# LKS_DEMO_V5_0.net
KiCad netlist of a schematic drawn in Altium Designer
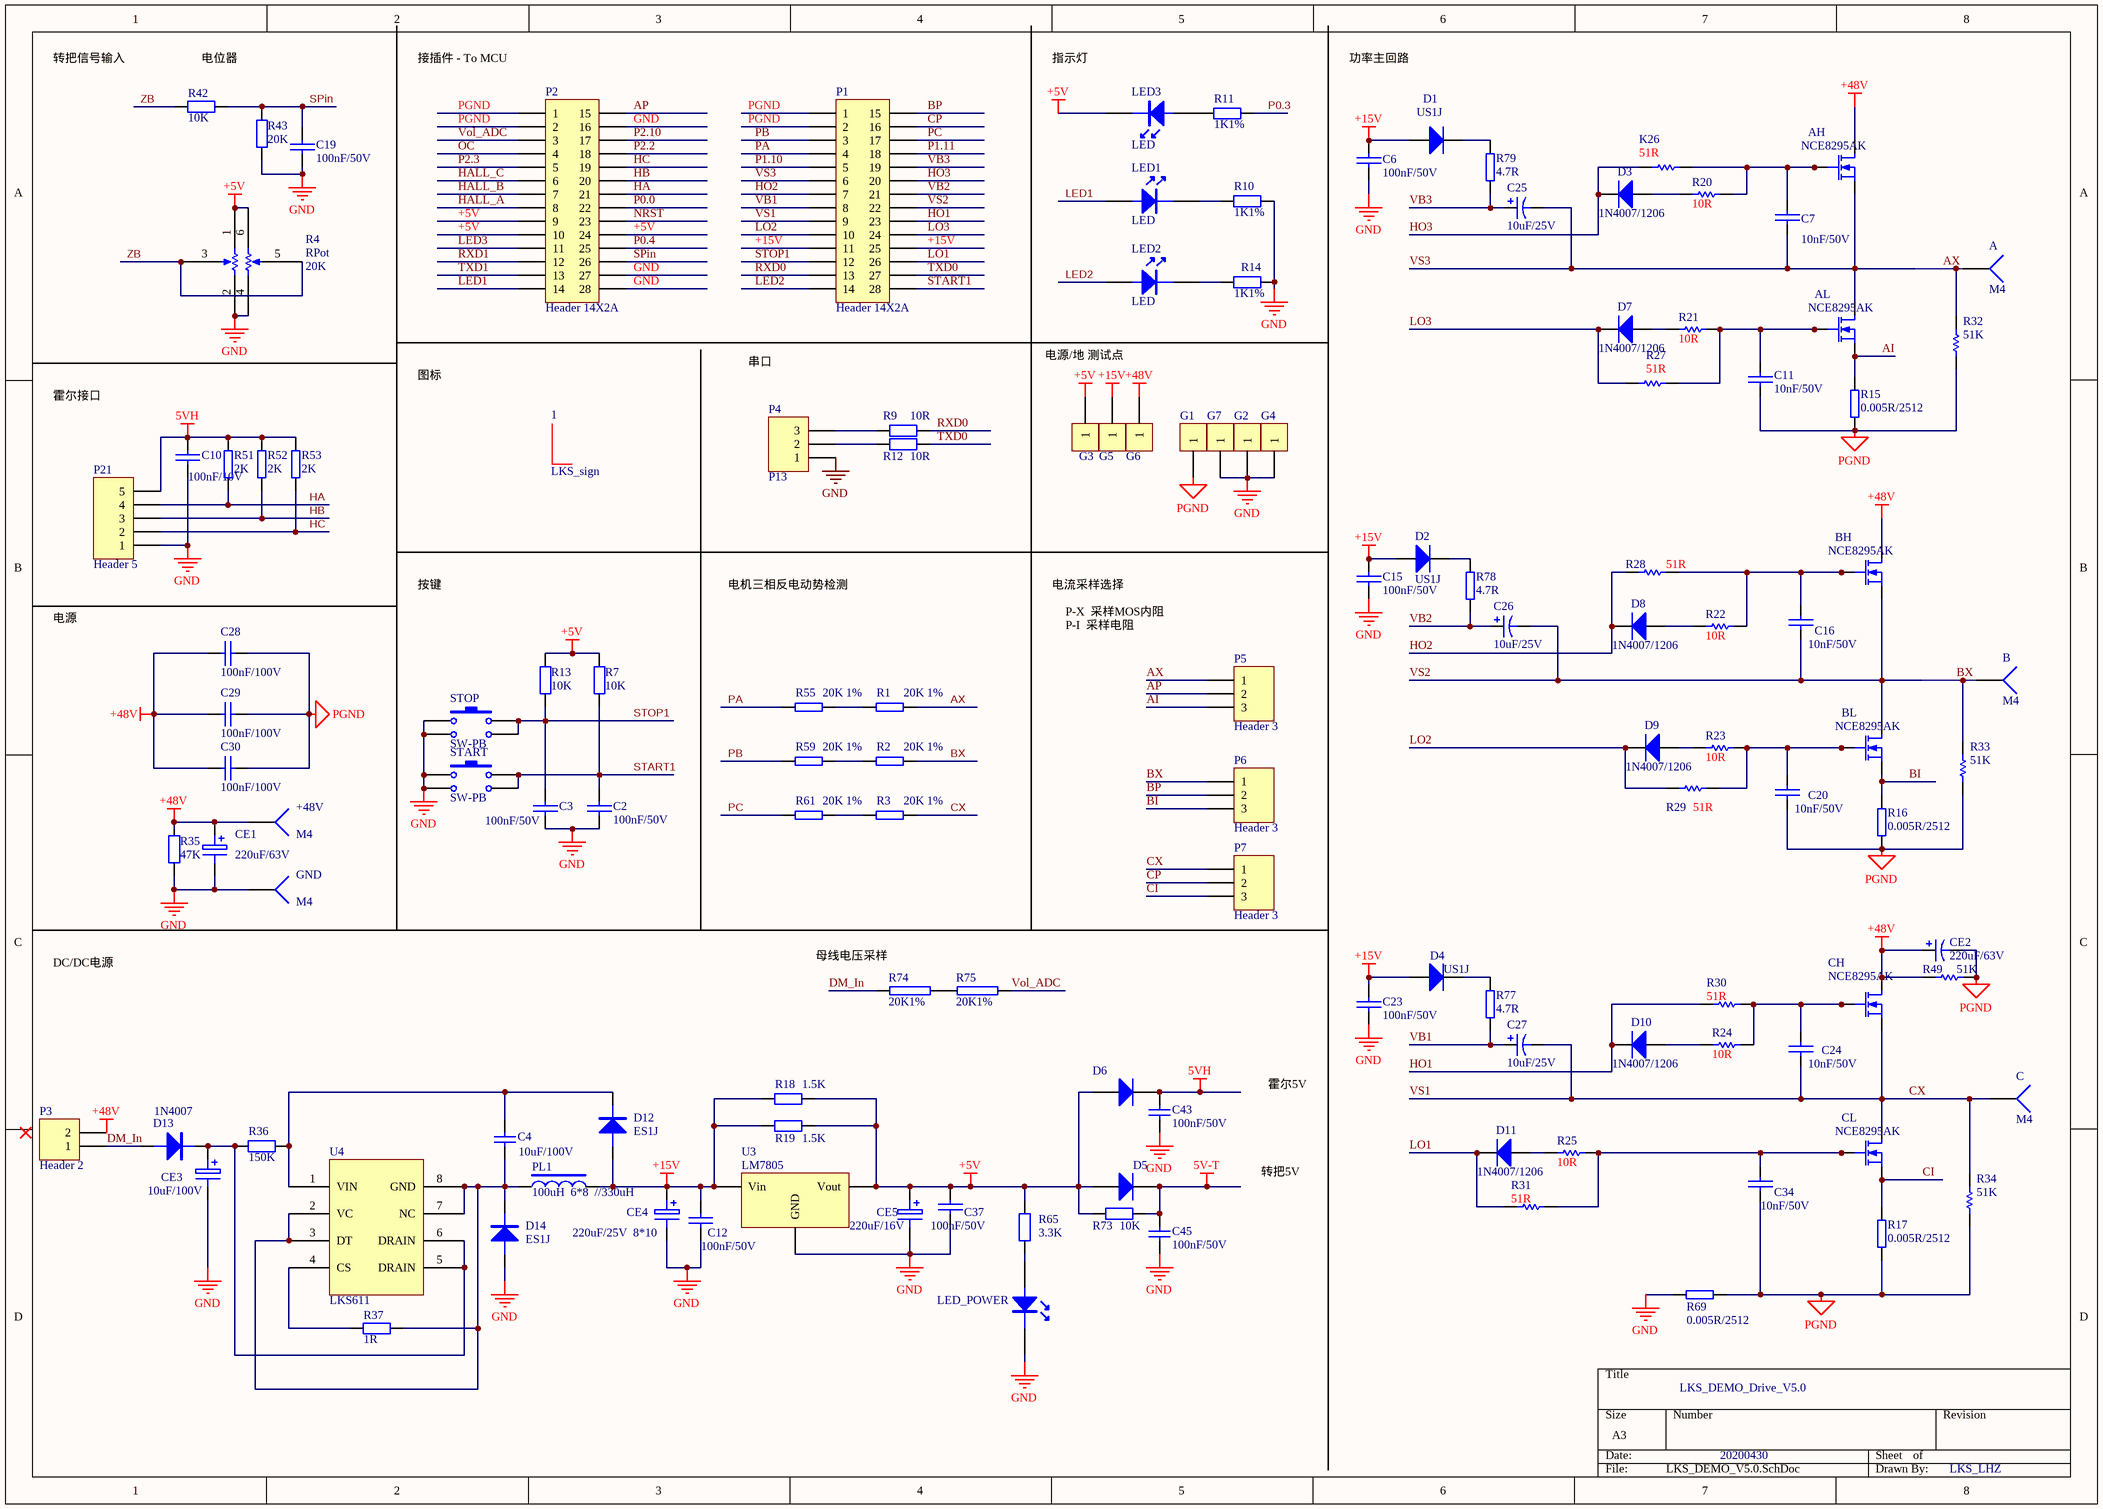
[diagram p0: LKS_DEMO_V5.0.SchDoc]

(export (version "E")
  (design (tool "Eeschema 10.0.6"))
  (components
    (comp (ref "+48V")
      (value "M4")
      (footprint "M4_Conector")
      (description "Socket")
      (fields (field (name "PUBLISHER") "Altium Limited"))
      (libsource (lib "*") (part "Socket"))
    )
    (comp (ref "1")
      (value "LKS_sign")
      (footprint "LKS_LOGO2")
      (libsource (lib "linko sch library") (part "LKS_sign"))
    )
    (comp (ref "A")
      (value "M4")
      (footprint "M4_Conector")
      (description "Socket")
      (fields (field (name "PUBLISHER") "Altium Limited"))
      (libsource (lib "*") (part "Socket"))
    )
    (comp (ref "AH")
      (value "NCE8295AK")
      (footprint "TO-252")
      (libsource (lib "POWER-conponent") (part "MOS"))
    )
    (comp (ref "AL")
      (value "NCE8295AK")
      (footprint "TO-252")
      (libsource (lib "POWER-conponent") (part "MOS"))
    )
    (comp (ref "B")
      (value "M4")
      (footprint "M4_Conector")
      (description "Socket")
      (fields (field (name "PUBLISHER") "Altium Limited"))
      (libsource (lib "*") (part "Socket"))
    )
    (comp (ref "BH")
      (value "NCE8295AK")
      (footprint "TO-252")
      (libsource (lib "POWER-conponent") (part "MOS"))
    )
    (comp (ref "BL")
      (value "NCE8295AK")
      (footprint "TO-252")
      (libsource (lib "POWER-conponent") (part "MOS"))
    )
    (comp (ref "C")
      (value "M4")
      (footprint "M4_Conector")
      (description "Socket")
      (fields (field (name "PUBLISHER") "Altium Limited"))
      (libsource (lib "*") (part "Socket"))
    )
    (comp (ref "C2")
      (value "100nF/50V")
      (footprint "0603C")
      (description "Capacitor")
      (libsource (lib "GJ-BC-IC") (part "CAP"))
    )
    (comp (ref "C3")
      (value "100nF/50V")
      (footprint "0603C")
      (description "Capacitor")
      (libsource (lib "GJ-BC-IC") (part "CAP"))
    )
    (comp (ref "C4")
      (value "10uF/100V")
      (footprint "1206")
      (description "Capacitor")
      (fields (field (name "PUBLISHER") "Altium Limited"))
      (libsource (lib "Miscellaneous Devices") (part "Cap"))
    )
    (comp (ref "C6")
      (value "100nF/50V")
      (footprint "0603C")
      (description "Capacitor")
      (libsource (lib "*") (part "C"))
    )
    (comp (ref "C7")
      (value "10nF/50V")
      (footprint "0603C")
      (description "Capacitor")
      (libsource (lib "") (part "CAP_1"))
    )
    (comp (ref "C10")
      (value "100nF/10V")
      (footprint "0603C")
      (description "Capacitor")
      (libsource (lib "GJ-BC-IC") (part "CAP"))
    )
    (comp (ref "C11")
      (value "10nF/50V")
      (footprint "0603C")
      (description "Capacitor")
      (libsource (lib "") (part "CAP_1"))
    )
    (comp (ref "C12")
      (value "100nF/50V")
      (footprint "0603C")
      (description "Capacitor")
      (libsource (lib "*") (part "CAP"))
    )
    (comp (ref "C15")
      (value "100nF/50V")
      (footprint "0603C")
      (description "Capacitor")
      (libsource (lib "*") (part "C"))
    )
    (comp (ref "C16")
      (value "10nF/50V")
      (footprint "0603C")
      (description "Capacitor")
      (libsource (lib "") (part "CAP_1"))
    )
    (comp (ref "C19")
      (value "100nF/50V")
      (footprint "0603C")
      (description "Capacitor")
      (libsource (lib "*") (part "C"))
    )
    (comp (ref "C20")
      (value "10nF/50V")
      (footprint "0603C")
      (description "Capacitor")
      (libsource (lib "") (part "CAP_1"))
    )
    (comp (ref "C23")
      (value "100nF/50V")
      (footprint "0603C")
      (description "Capacitor")
      (libsource (lib "*") (part "C"))
    )
    (comp (ref "C24")
      (value "10nF/50V")
      (footprint "0603C")
      (description "Capacitor")
      (libsource (lib "") (part "CAP_1"))
    )
    (comp (ref "C25")
      (value "10uF/25V")
      (footprint "1206")
      (description "Polarized Capacitor (Radial)")
      (fields (field (name "PUBLISHER") "Altium Limited"))
      (libsource (lib "*") (part "Cap Pol1"))
    )
    (comp (ref "C26")
      (value "10uF/25V")
      (footprint "1206")
      (description "Polarized Capacitor (Radial)")
      (fields (field (name "PUBLISHER") "Altium Limited"))
      (libsource (lib "*") (part "Cap Pol1"))
    )
    (comp (ref "C27")
      (value "10uF/25V")
      (footprint "1206")
      (description "Polarized Capacitor (Radial)")
      (fields (field (name "PUBLISHER") "Altium Limited"))
      (libsource (lib "*") (part "Cap Pol1"))
    )
    (comp (ref "C28")
      (value "100nF/100V")
      (footprint "0805C")
      (description "Capacitor")
      (libsource (lib "*") (part "CAP"))
    )
    (comp (ref "C29")
      (value "100nF/100V")
      (footprint "0805C")
      (description "Capacitor")
      (libsource (lib "*") (part "CAP"))
    )
    (comp (ref "C30")
      (value "100nF/100V")
      (footprint "0805C")
      (description "Capacitor")
      (libsource (lib "*") (part "CAP"))
    )
    (comp (ref "C34")
      (value "10nF/50V")
      (footprint "0603C")
      (description "Capacitor")
      (libsource (lib "") (part "CAP_1"))
    )
    (comp (ref "C37")
      (value "100nF/50V")
      (footprint "0603C")
      (description "Capacitor")
      (libsource (lib "*") (part "C"))
    )
    (comp (ref "C43")
      (value "100nF/50V")
      (footprint "0603C")
      (description "Capacitor")
      (fields (field (name "PUBLISHER") "Altium Limited"))
      (libsource (lib "Miscellaneous Devices") (part "Cap"))
    )
    (comp (ref "C45")
      (value "100nF/50V")
      (footprint "0603C")
      (description "Capacitor")
      (fields (field (name "PUBLISHER") "Altium Limited"))
      (libsource (lib "Miscellaneous Devices") (part "Cap"))
    )
    (comp (ref "CE1")
      (value "220uF/63V")
      (footprint "220uF/25V 12.5*12.5")
      (description "Electrolytic Capacitor")
      (libsource (lib "*") (part "CD"))
    )
    (comp (ref "CE2")
      (value "220uF/63V")
      (footprint "220uF/25V 12.5*12.5")
      (description "Polarized Capacitor (Radial)")
      (fields (field (name "PUBLISHER") "Altium Limited"))
      (libsource (lib "Miscellaneous Devices") (part "Cap Pol1"))
    )
    (comp (ref "CE3")
      (value "10uF/100V")
      (footprint "220UF/25V paster8*10")
      (description "Electrolytic Capacitor")
      (libsource (lib "*") (part "CD"))
    )
    (comp (ref "CE4")
      (value "220uF/25V  8*10")
      (footprint "220UF/25V paster8*10")
      (description "Electrolytic Capacitor")
      (libsource (lib "*") (part "CD"))
    )
    (comp (ref "CE5")
      (value "220uF/16V")
      (footprint "220UF/16V paster6.3*7.7 - duplicate")
      (description "Electrolytic Capacitor")
      (libsource (lib "*") (part "CD"))
    )
    (comp (ref "CH")
      (value "NCE8295AK")
      (footprint "TO-252")
      (libsource (lib "POWER-conponent") (part "MOS"))
    )
    (comp (ref "CL")
      (value "NCE8295AK")
      (footprint "TO-252")
      (libsource (lib "POWER-conponent") (part "MOS"))
    )
    (comp (ref "D1")
      (value "US1J")
      (footprint "SMA金丰")
      (description "Default Diode")
      (fields (field (name "PUBLISHER") "Altium Limited"))
      (libsource (lib "*") (part "Diode"))
    )
    (comp (ref "D2")
      (value "US1J")
      (footprint "SMA金丰")
      (description "Default Diode")
      (fields (field (name "PUBLISHER") "Altium Limited"))
      (libsource (lib "*") (part "Diode"))
    )
    (comp (ref "D3")
      (value "1N4007/1206")
      (footprint "D1206")
      (description "Default Diode")
      (fields (field (name "PUBLISHER") "Altium Limited"))
      (libsource (lib "*") (part "Diode"))
    )
    (comp (ref "D4")
      (value "US1J")
      (footprint "SMA金丰")
      (description "Default Diode")
      (fields (field (name "PUBLISHER") "Altium Limited"))
      (libsource (lib "*") (part "Diode"))
    )
    (comp (ref "D5")
      (value "1N4007")
      (footprint "D1206")
      (description "1 Amp General Purpose Rectifier")
      (fields (field (name "PUBLISHER") "Altium Limited"))
      (libsource (lib "Miscellaneous Devices") (part "Diode 1N4007"))
    )
    (comp (ref "D6")
      (value "1N4007")
      (footprint "D1206")
      (description "1 Amp General Purpose Rectifier")
      (fields (field (name "PUBLISHER") "Altium Limited"))
      (libsource (lib "Miscellaneous Devices") (part "Diode 1N4007"))
    )
    (comp (ref "D7")
      (value "1N4007/1206")
      (footprint "D1206")
      (description "Default Diode")
      (fields (field (name "PUBLISHER") "Altium Limited"))
      (libsource (lib "*") (part "Diode"))
    )
    (comp (ref "D8")
      (value "1N4007/1206")
      (footprint "D1206")
      (description "Default Diode")
      (fields (field (name "PUBLISHER") "Altium Limited"))
      (libsource (lib "*") (part "Diode"))
    )
    (comp (ref "D9")
      (value "1N4007/1206")
      (footprint "D1206")
      (description "Default Diode")
      (fields (field (name "PUBLISHER") "Altium Limited"))
      (libsource (lib "*") (part "Diode"))
    )
    (comp (ref "D10")
      (value "1N4007/1206")
      (footprint "D1206")
      (description "Default Diode")
      (fields (field (name "PUBLISHER") "Altium Limited"))
      (libsource (lib "*") (part "Diode"))
    )
    (comp (ref "D11")
      (value "1N4007/1206")
      (footprint "D1206")
      (description "Default Diode")
      (fields (field (name "PUBLISHER") "Altium Limited"))
      (libsource (lib "*") (part "Diode"))
    )
    (comp (ref "D12")
      (value "ES1J")
      (footprint "DO-214AC")
      (description "Diode")
      (libsource (lib "*") (part "D"))
    )
    (comp (ref "D13")
      (value "1N4007")
      (footprint "DO-214AC")
      (description "Diode")
      (libsource (lib "*") (part "D"))
    )
    (comp (ref "D14")
      (value "ES1J")
      (footprint "DO-214AC")
      (description "Diode")
      (libsource (lib "*") (part "D"))
    )
    (comp (ref "G1")
      (value "PAD1.2")
      (footprint "PAD1.2")
      (description "Connector")
      (libsource (lib "") (part "CON1_1"))
    )
    (comp (ref "G2")
      (value "PAD1.2")
      (footprint "PAD1.2")
      (description "Connector")
      (libsource (lib "") (part "CON1_1"))
    )
    (comp (ref "G3")
      (value "PAD1.2")
      (footprint "PAD1.2")
      (description "Connector")
      (libsource (lib "*") (part "CON1"))
    )
    (comp (ref "G4")
      (value "PAD1.2")
      (footprint "PAD1.2")
      (description "Connector")
      (libsource (lib "") (part "CON1_1"))
    )
    (comp (ref "G5")
      (value "PAD1.2")
      (footprint "PAD1.2")
      (description "Connector")
      (libsource (lib "*") (part "CON1"))
    )
    (comp (ref "G6")
      (value "PAD1.2")
      (footprint "PAD1.2")
      (description "Connector")
      (libsource (lib "*") (part "CON1"))
    )
    (comp (ref "G7")
      (value "PAD1.2")
      (footprint "PAD1.2")
      (description "Connector")
      (libsource (lib "") (part "CON1_1"))
    )
    (comp (ref "GND")
      (value "M4")
      (footprint "M4_Conector")
      (description "Socket")
      (fields (field (name "PUBLISHER") "Altium Limited"))
      (libsource (lib "*") (part "Socket"))
    )
    (comp (ref "K26")
      (value "51R")
      (footprint "0805R")
      (description "Resistor")
      (fields (field (name "PUBLISHER") "Altium Limited"))
      (libsource (lib "*") (part "Res1"))
    )
    (comp (ref "LED1") (value "LED") (footprint "SOD323") (libsource (lib "GJ-BC-IC") (part "LED")))
    (comp (ref "LED2") (value "LED") (footprint "SOD323") (libsource (lib "GJ-BC-IC") (part "LED")))
    (comp (ref "LED3") (value "LED") (footprint "SOD323") (libsource (lib "GJ-BC-IC") (part "LED")))
    (comp (ref "LED_POWER") (value "LED_R") (footprint "SOD323") (libsource (lib "*") (part "LED")))
    (comp (ref "P1")
      (value "Header 14X2A")
      (footprint "HDR2X14_CEN")
      (description "Header, 14-Pin, Dual row")
      (fields (field (name "PUBLISHER") "Altium Limited"))
      (libsource (lib "Miscellaneous Connectors") (part "Header 14X2A"))
    )
    (comp (ref "P2")
      (value "Header 14X2A")
      (footprint "HDR2X14_CEN")
      (description "Header, 14-Pin, Dual row")
      (fields (field (name "PUBLISHER") "Altium Limited"))
      (libsource (lib "Miscellaneous Connectors") (part "Header 14X2A"))
    )
    (comp (ref "P3")
      (value "Header 2")
      (footprint "HDR1X2")
      (description "Header, 2-Pin")
      (fields (field (name "PUBLISHER") "Altium Limited"))
      (libsource (lib "Miscellaneous Connectors") (part "Header 2"))
    )
    (comp (ref "P4")
      (value "P13")
      (footprint "2.54-XH-3A-180")
      (description "Header, 3-Pin")
      (fields (field (name "PUBLISHER") "Altium Limited"))
      (libsource (lib "") (part "Header 3_1"))
    )
    (comp (ref "P5")
      (value "Header 3")
      (footprint "HDR1X3")
      (description "Header, 3-Pin")
      (fields (field (name "PUBLISHER") "Altium Limited"))
      (libsource (lib "Miscellaneous Connectors") (part "Header 3"))
    )
    (comp (ref "P6")
      (value "Header 3")
      (footprint "HDR1X3")
      (description "Header, 3-Pin")
      (fields (field (name "PUBLISHER") "Altium Limited"))
      (libsource (lib "Miscellaneous Connectors") (part "Header 3"))
    )
    (comp (ref "P7")
      (value "Header 3")
      (footprint "HDR1X3")
      (description "Header, 3-Pin")
      (fields (field (name "PUBLISHER") "Altium Limited"))
      (libsource (lib "Miscellaneous Connectors") (part "Header 3"))
    )
    (comp (ref "P21")
      (value "Header 5")
      (footprint "2.54-XH-5A-180")
      (description "Header, 5-Pin")
      (fields (field (name "PUBLISHER") "Altium Limited"))
      (libsource (lib "Miscellaneous Connectors") (part "Header 5"))
    )
    (comp (ref "PL1")
      (value "100uH  6*8  //330uH")
      (footprint "L_DIP_6*8MM")
      (libsource (lib "*") (part "L"))
    )
    (comp (ref "R1") (value "20K 1%") (footprint "0805R") (libsource (lib "HenterLi") (part "RES/1")))
    (comp (ref "R2") (value "20K 1%") (footprint "0805R") (libsource (lib "HenterLi") (part "RES/1")))
    (comp (ref "R3") (value "20K 1%") (footprint "0805R") (libsource (lib "HenterLi") (part "RES/1")))
    (comp (ref "R4")
      (value "RPot")
      (footprint "RK097-W")
      (description "Potentiometer")
      (fields (field (name "ALTIUM_VALUE") "20K") (field (name "PUBLISHER") "Altium Limited"))
      (libsource (lib "LKS_DEMO_V5.0") (part "RPot"))
    )
    (comp (ref "R7")
      (value "10K")
      (footprint "0603R")
      (description "Resistor")
      (fields (field (name "PUBLISHER") "Altium Limited"))
      (libsource (lib "") (part "Res2_2"))
    )
    (comp (ref "R9")
      (value "10R")
      (footprint "0603R")
      (description "Resistor")
      (fields (field (name "PUBLISHER") "Altium Limited"))
      (libsource (lib "Miscellaneous Devices") (part "Res2"))
    )
    (comp (ref "R10")
      (value "1K1%")
      (footprint "0603R")
      (description "Resistor")
      (fields (field (name "PUBLISHER") "Altium Limited"))
      (libsource (lib "GJ-BC-IC") (part "Res2"))
    )
    (comp (ref "R11")
      (value "1K1%")
      (footprint "0603R")
      (description "Resistor")
      (fields (field (name "PUBLISHER") "Altium Limited"))
      (libsource (lib "GJ-BC-IC") (part "Res2"))
    )
    (comp (ref "R12")
      (value "10R")
      (footprint "0603R")
      (description "Resistor")
      (fields (field (name "PUBLISHER") "Altium Limited"))
      (libsource (lib "") (part "Res2_3"))
    )
    (comp (ref "R13")
      (value "10K")
      (footprint "0603R")
      (description "Resistor")
      (fields (field (name "PUBLISHER") "Altium Limited"))
      (libsource (lib "") (part "Res2_1"))
    )
    (comp (ref "R14")
      (value "1K1%")
      (footprint "0603R")
      (description "Resistor")
      (fields (field (name "PUBLISHER") "Altium Limited"))
      (libsource (lib "GJ-BC-IC") (part "Res2"))
    )
    (comp (ref "R15") (value "0.005R/2512") (footprint "2512") (libsource (lib "*") (part "RES2短")))
    (comp (ref "R16") (value "0.005R/2512") (footprint "2512") (libsource (lib "*") (part "RES2短")))
    (comp (ref "R17") (value "0.005R/2512") (footprint "2512") (libsource (lib "*") (part "RES2短")))
    (comp (ref "R18")
      (value "1.5K")
      (footprint "0805R")
      (description "Resistor")
      (fields (field (name "PUBLISHER") "Altium Limited"))
      (libsource (lib "LINKO_V1.0") (part "Res"))
    )
    (comp (ref "R19")
      (value "1.5K")
      (footprint "0805R")
      (description "Resistor")
      (fields (field (name "PUBLISHER") "Altium Limited"))
      (libsource (lib "LINKO_V1.0") (part "Res"))
    )
    (comp (ref "R20")
      (value "10R")
      (footprint "0805R")
      (description "Resistor")
      (fields (field (name "PUBLISHER") "Altium Limited"))
      (libsource (lib "*") (part "Res1"))
    )
    (comp (ref "R21")
      (value "10R")
      (footprint "0805R")
      (description "Resistor")
      (fields (field (name "PUBLISHER") "Altium Limited"))
      (libsource (lib "*") (part "Res1"))
    )
    (comp (ref "R22")
      (value "10R")
      (footprint "0805R")
      (description "Resistor")
      (fields (field (name "PUBLISHER") "Altium Limited"))
      (libsource (lib "*") (part "Res1"))
    )
    (comp (ref "R23")
      (value "10R")
      (footprint "0805R")
      (description "Resistor")
      (fields (field (name "PUBLISHER") "Altium Limited"))
      (libsource (lib "*") (part "Res1"))
    )
    (comp (ref "R24")
      (value "10R")
      (footprint "0805R")
      (description "Resistor")
      (fields (field (name "PUBLISHER") "Altium Limited"))
      (libsource (lib "*") (part "Res1"))
    )
    (comp (ref "R25")
      (value "10R")
      (footprint "0805R")
      (description "Resistor")
      (fields (field (name "PUBLISHER") "Altium Limited"))
      (libsource (lib "*") (part "Res1"))
    )
    (comp (ref "R27")
      (value "51R")
      (footprint "0805R")
      (description "Resistor")
      (fields (field (name "PUBLISHER") "Altium Limited"))
      (libsource (lib "*") (part "Res1"))
    )
    (comp (ref "R28")
      (value "51R")
      (footprint "0805R")
      (description "Resistor")
      (fields (field (name "PUBLISHER") "Altium Limited"))
      (libsource (lib "*") (part "Res1"))
    )
    (comp (ref "R29")
      (value "51R")
      (footprint "0805R")
      (description "Resistor")
      (fields (field (name "PUBLISHER") "Altium Limited"))
      (libsource (lib "*") (part "Res1"))
    )
    (comp (ref "R30")
      (value "51R")
      (footprint "0805R")
      (description "Resistor")
      (fields (field (name "PUBLISHER") "Altium Limited"))
      (libsource (lib "*") (part "Res1"))
    )
    (comp (ref "R31")
      (value "51R")
      (footprint "0805R")
      (description "Resistor")
      (fields (field (name "PUBLISHER") "Altium Limited"))
      (libsource (lib "*") (part "Res1"))
    )
    (comp (ref "R32")
      (value "51K")
      (footprint "0805R")
      (description "Resistor")
      (fields (field (name "PUBLISHER") "Altium Limited"))
      (libsource (lib "*") (part "Res1"))
    )
    (comp (ref "R33")
      (value "51K")
      (footprint "0805R")
      (description "Resistor")
      (fields (field (name "PUBLISHER") "Altium Limited"))
      (libsource (lib "*") (part "Res1"))
    )
    (comp (ref "R34")
      (value "51K")
      (footprint "0805R")
      (description "Resistor")
      (fields (field (name "PUBLISHER") "Altium Limited"))
      (libsource (lib "*") (part "Res1"))
    )
    (comp (ref "R35")
      (value "47K")
      (footprint "1206R")
      (description "Resistor")
      (fields (field (name "PUBLISHER") "Altium Limited"))
      (libsource (lib "") (part "Res_2"))
    )
    (comp (ref "R36")
      (value "150K")
      (footprint "0805R")
      (description "Resistor")
      (fields (field (name "PUBLISHER") "Altium Limited"))
      (libsource (lib "") (part "Res2_1"))
    )
    (comp (ref "R37")
      (value "1R")
      (footprint "1206")
      (description "Resistor")
      (fields (field (name "PUBLISHER") "Altium Limited"))
      (libsource (lib "") (part "Res2_2"))
    )
    (comp (ref "R42")
      (value "10K")
      (footprint "0603R")
      (description "Resistor")
      (fields (field (name "PUBLISHER") "Altium Limited"))
      (libsource (lib "LINKO_V1.0") (part "Res"))
    )
    (comp (ref "R43")
      (value "20K")
      (footprint "0603R")
      (description "Resistor")
      (fields (field (name "PUBLISHER") "Altium Limited"))
      (libsource (lib "") (part "Res_1"))
    )
    (comp (ref "R49")
      (value "51K")
      (footprint "0805R")
      (description "Resistor")
      (fields (field (name "PUBLISHER") "Altium Limited"))
      (libsource (lib "*") (part "Res1"))
    )
    (comp (ref "R51") (value "2K") (footprint "0603R") (libsource (lib "") (part "RES/1_1")))
    (comp (ref "R52") (value "2K") (footprint "0603R") (libsource (lib "") (part "RES/1_1")))
    (comp (ref "R53") (value "2K") (footprint "0603R") (libsource (lib "") (part "RES/1_1")))
    (comp (ref "R55") (value "20K 1%") (footprint "0805R") (libsource (lib "HenterLi") (part "RES/1")))
    (comp (ref "R59") (value "20K 1%") (footprint "0805R") (libsource (lib "HenterLi") (part "RES/1")))
    (comp (ref "R61") (value "20K 1%") (footprint "0805R") (libsource (lib "HenterLi") (part "RES/1")))
    (comp (ref "R65")
      (value "3.3K")
      (footprint "0603R")
      (description "Resistor")
      (fields (field (name "PUBLISHER") "Altium Limited"))
      (libsource (lib "Miscellaneous Devices") (part "Res2"))
    )
    (comp (ref "R69") (value "0.005R/2512") (footprint "2512") (libsource (lib "*") (part "RES2短")))
    (comp (ref "R73")
      (value "10K")
      (footprint "0603R")
      (description "Resistor")
      (fields (field (name "PUBLISHER") "Altium Limited"))
      (libsource (lib "") (part "Res2_2"))
    )
    (comp (ref "R74") (value "20K1%") (footprint "0603R") (libsource (lib "*") (part "R")))
    (comp (ref "R75") (value "20K1%") (footprint "0603R") (libsource (lib "*") (part "R")))
    (comp (ref "R77") (value "4.7R") (footprint "0805r") (libsource (lib "*") (part "RES2短")))
    (comp (ref "R78") (value "4.7R") (footprint "0805r") (libsource (lib "*") (part "RES2短")))
    (comp (ref "R79") (value "4.7R") (footprint "0805r") (libsource (lib "*") (part "RES2短")))
    (comp (ref "START")
      (value "SW-PB")
      (footprint "SW-PB  12*12")
      (description "Switch")
      (fields (field (name "PUBLISHER") "Altium Limited"))
      (libsource (lib "LKS_DEMO_081_V4.0") (part "SW-PB"))
    )
    (comp (ref "STOP")
      (value "SW-PB")
      (footprint "SW-PB  12*12")
      (description "Switch")
      (fields (field (name "PUBLISHER") "Altium Limited"))
      (libsource (lib "LKS_DEMO_081_V4.0") (part "SW-PB"))
    )
    (comp (ref "U3")
      (value "LM7805")
      (footprint "linko pcb library:SOT-89")
      (libsource (lib "*") (part "VOL-78"))
    )
    (comp (ref "U4") (value "LKS611") (libsource (lib "linko sch library") (part "LKS611")))
  )
  (nets
    (net (code "1") (name "+5V") (class "Default")
      (node (ref "C37") (pin "2") (pinfunction "2_2") (pintype "passive"))
      (node (ref "CE5") (pin "1") (pinfunction "1_1") (pintype "passive"))
      (node (ref "D5") (pin "1") (pinfunction "A_1") (pintype "passive"))
      (node (ref "D6") (pin "1") (pinfunction "A_1") (pintype "passive"))
      (node (ref "G3") (pin "1") (pinfunction "1_1") (pintype "passive"))
      (node (ref "LED3") (pin "2") (pinfunction "K_2") (pintype "passive"))
      (node (ref "P2") (pin "10") (pinfunction "10_10") (pintype "passive"))
      (node (ref "P2") (pin "24") (pinfunction "24_24") (pintype "passive"))
      (node (ref "P2") (pin "9") (pinfunction "9_9") (pintype "passive"))
      (node (ref "R13") (pin "2") (pinfunction "2_2") (pintype "passive"))
      (node (ref "R18") (pin "2") (pinfunction "2_2") (pintype "passive"))
      (node (ref "R19") (pin "2") (pinfunction "2_2") (pintype "passive"))
      (node (ref "R4") (pin "1") (pinfunction "TOP_1") (pintype "passive"))
      (node (ref "R4") (pin "6") (pinfunction "TOP_6") (pintype "passive"))
      (node (ref "R65") (pin "1") (pinfunction "1_1") (pintype "passive"))
      (node (ref "R7") (pin "1") (pinfunction "1_1") (pintype "passive"))
      (node (ref "R73") (pin "1") (pinfunction "1_1") (pintype "passive"))
      (node (ref "U3") (pin "1") (pinfunction "Vout_1") (pintype "passive"))
    )
    (net (code "2") (name "+15V") (class "Default")
      (node (ref "C12") (pin "1") (pinfunction "1_1") (pintype "passive"))
      (node (ref "C15") (pin "2") (pinfunction "2_2") (pintype "passive"))
      (node (ref "C23") (pin "2") (pinfunction "2_2") (pintype "passive"))
      (node (ref "C6") (pin "2") (pinfunction "2_2") (pintype "passive"))
      (node (ref "CE4") (pin "1") (pinfunction "1_1") (pintype "passive"))
      (node (ref "D1") (pin "1") (pinfunction "A_1") (pintype "passive"))
      (node (ref "D12") (pin "1") (pinfunction "1_1") (pintype "passive"))
      (node (ref "D2") (pin "1") (pinfunction "A_1") (pintype "passive"))
      (node (ref "D4") (pin "1") (pinfunction "A_1") (pintype "passive"))
      (node (ref "G5") (pin "1") (pinfunction "1_1") (pintype "passive"))
      (node (ref "P1") (pin "11") (pinfunction "11_11") (pintype "passive"))
      (node (ref "P1") (pin "25") (pinfunction "25_25") (pintype "passive"))
      (node (ref "PL1") (pin "1") (pinfunction "1_1") (pintype "passive"))
      (node (ref "R18") (pin "1") (pinfunction "1_1") (pintype "passive"))
      (node (ref "R19") (pin "1") (pinfunction "1_1") (pintype "passive"))
      (node (ref "U3") (pin "3") (pinfunction "Vin_3") (pintype "passive"))
    )
    (net (code "3") (name "+48V") (class "Default")
      (node (ref "+48V") (pin "1") (pinfunction "1_1") (pintype "passive"))
      (node (ref "AH") (pin "2") (pinfunction "D_2") (pintype "passive"))
      (node (ref "BH") (pin "2") (pinfunction "D_2") (pintype "passive"))
      (node (ref "C28") (pin "2") (pinfunction "2_2") (pintype "passive"))
      (node (ref "C29") (pin "2") (pinfunction "2_2") (pintype "passive"))
      (node (ref "C30") (pin "2") (pinfunction "2_2") (pintype "passive"))
      (node (ref "CE1") (pin "1") (pinfunction "1_1") (pintype "passive"))
      (node (ref "CE2") (pin "1") (pinfunction "1_1") (pintype "passive"))
      (node (ref "CH") (pin "2") (pinfunction "D_2") (pintype "passive"))
      (node (ref "G6") (pin "1") (pinfunction "1_1") (pintype "passive"))
      (node (ref "P3") (pin "2") (pinfunction "2_2") (pintype "passive"))
      (node (ref "R35") (pin "1") (pinfunction "1_1") (pintype "passive"))
      (node (ref "R49") (pin "1") (pinfunction "1_1") (pintype "passive"))
    )
    (net (code "4") (name "/AI") (class "Default")
      (node (ref "AL") (pin "3") (pinfunction "S_3") (pintype "passive"))
      (node (ref "P5") (pin "3") (pinfunction "3_3") (pintype "passive"))
      (node (ref "R15") (pin "1") (pinfunction "1_1") (pintype "passive"))
    )
    (net (code "5") (name "/AP") (class "Default")
      (node (ref "P2") (pin "15") (pinfunction "15_15") (pintype "passive"))
      (node (ref "P5") (pin "2") (pinfunction "2_2") (pintype "passive"))
    )
    (net (code "6") (name "/AX") (class "Default")
      (node (ref "A") (pin "1") (pinfunction "1_1") (pintype "passive"))
      (node (ref "AH") (pin "3") (pinfunction "S_3") (pintype "passive"))
      (node (ref "AL") (pin "2") (pinfunction "D_2") (pintype "passive"))
      (node (ref "C25") (pin "2") (pinfunction "2_2") (pintype "passive"))
      (node (ref "C7") (pin "2") (pinfunction "2_2") (pintype "passive"))
      (node (ref "P1") (pin "6") (pinfunction "6_6") (pintype "passive"))
      (node (ref "P5") (pin "1") (pinfunction "1_1") (pintype "passive"))
      (node (ref "R1") (pin "2") (pinfunction "2_2") (pintype "passive"))
      (node (ref "R32") (pin "2") (pinfunction "2_2") (pintype "passive"))
    )
    (net (code "7") (name "/BI") (class "Default")
      (node (ref "BL") (pin "3") (pinfunction "S_3") (pintype "passive"))
      (node (ref "P6") (pin "3") (pinfunction "3_3") (pintype "passive"))
      (node (ref "R16") (pin "2") (pinfunction "2_2") (pintype "passive"))
    )
    (net (code "8") (name "/BP") (class "Default")
      (node (ref "P1") (pin "15") (pinfunction "15_15") (pintype "passive"))
      (node (ref "P6") (pin "2") (pinfunction "2_2") (pintype "passive"))
    )
    (net (code "9") (name "/BX") (class "Default")
      (node (ref "B") (pin "1") (pinfunction "1_1") (pintype "passive"))
      (node (ref "BH") (pin "3") (pinfunction "S_3") (pintype "passive"))
      (node (ref "BL") (pin "2") (pinfunction "D_2") (pintype "passive"))
      (node (ref "C16") (pin "2") (pinfunction "2_2") (pintype "passive"))
      (node (ref "C26") (pin "2") (pinfunction "2_2") (pintype "passive"))
      (node (ref "P1") (pin "22") (pinfunction "22_22") (pintype "passive"))
      (node (ref "P6") (pin "1") (pinfunction "1_1") (pintype "passive"))
      (node (ref "R2") (pin "2") (pinfunction "2_2") (pintype "passive"))
      (node (ref "R33") (pin "2") (pinfunction "2_2") (pintype "passive"))
    )
    (net (code "10") (name "/CI") (class "Default")
      (node (ref "CL") (pin "3") (pinfunction "S_3") (pintype "passive"))
      (node (ref "P7") (pin "3") (pinfunction "3_3") (pintype "passive"))
      (node (ref "R17") (pin "1") (pinfunction "1_1") (pintype "passive"))
    )
    (net (code "11") (name "/CP") (class "Default")
      (node (ref "P1") (pin "16") (pinfunction "16_16") (pintype "passive"))
      (node (ref "P7") (pin "2") (pinfunction "2_2") (pintype "passive"))
    )
    (net (code "12") (name "/CX") (class "Default")
      (node (ref "C") (pin "1") (pinfunction "1_1") (pintype "passive"))
      (node (ref "C24") (pin "2") (pinfunction "2_2") (pintype "passive"))
      (node (ref "C27") (pin "2") (pinfunction "2_2") (pintype "passive"))
      (node (ref "CH") (pin "3") (pinfunction "S_3") (pintype "passive"))
      (node (ref "CL") (pin "2") (pinfunction "D_2") (pintype "passive"))
      (node (ref "P1") (pin "9") (pinfunction "9_9") (pintype "passive"))
      (node (ref "P7") (pin "1") (pinfunction "1_1") (pintype "passive"))
      (node (ref "R3") (pin "2") (pinfunction "2_2") (pintype "passive"))
      (node (ref "R34") (pin "2") (pinfunction "2_2") (pintype "passive"))
    )
    (net (code "13") (name "/DM_In") (class "Default")
      (node (ref "D13") (pin "1") (pinfunction "1_1") (pintype "passive"))
      (node (ref "P3") (pin "1") (pinfunction "1_1") (pintype "passive"))
      (node (ref "R74") (pin "1") (pinfunction "1_1") (pintype "passive"))
    )
    (net (code "14") (name "/HA") (class "Default")
      (node (ref "P2") (pin "21") (pinfunction "21_21") (pintype "passive"))
      (node (ref "P21") (pin "4") (pinfunction "4_4") (pintype "passive"))
      (node (ref "R51") (pin "1") (pinfunction "1_1") (pintype "passive"))
    )
    (net (code "15") (name "/HALL_A") (class "Default")
      (node (ref "P2") (pin "8") (pinfunction "8_8") (pintype "passive"))
    )
    (net (code "16") (name "/HALL_B") (class "Default")
      (node (ref "P2") (pin "7") (pinfunction "7_7") (pintype "passive"))
    )
    (net (code "17") (name "/HALL_C") (class "Default")
      (node (ref "P2") (pin "6") (pinfunction "6_6") (pintype "passive"))
    )
    (net (code "18") (name "/HB") (class "Default")
      (node (ref "P2") (pin "20") (pinfunction "20_20") (pintype "passive"))
      (node (ref "P21") (pin "3") (pinfunction "3_3") (pintype "passive"))
      (node (ref "R52") (pin "1") (pinfunction "1_1") (pintype "passive"))
    )
    (net (code "19") (name "/HC") (class "Default")
      (node (ref "P2") (pin "19") (pinfunction "19_19") (pintype "passive"))
      (node (ref "P21") (pin "2") (pinfunction "2_2") (pintype "passive"))
      (node (ref "R53") (pin "1") (pinfunction "1_1") (pintype "passive"))
    )
    (net (code "20") (name "/HO1") (class "Default")
      (node (ref "D10") (pin "2") (pinfunction "K_2") (pintype "passive"))
      (node (ref "P1") (pin "23") (pinfunction "23_23") (pintype "passive"))
      (node (ref "R30") (pin "1") (pinfunction "1_1") (pintype "passive"))
    )
    (net (code "21") (name "/HO2") (class "Default")
      (node (ref "D8") (pin "2") (pinfunction "K_2") (pintype "passive"))
      (node (ref "P1") (pin "7") (pinfunction "7_7") (pintype "passive"))
      (node (ref "R28") (pin "1") (pinfunction "1_1") (pintype "passive"))
    )
    (net (code "22") (name "/HO3") (class "Default")
      (node (ref "D3") (pin "2") (pinfunction "K_2") (pintype "passive"))
      (node (ref "K26") (pin "1") (pinfunction "1_1") (pintype "passive"))
      (node (ref "P1") (pin "20") (pinfunction "20_20") (pintype "passive"))
    )
    (net (code "23") (name "/LED1") (class "Default")
      (node (ref "LED1") (pin "1") (pinfunction "A_1") (pintype "passive"))
      (node (ref "P2") (pin "14") (pinfunction "14_14") (pintype "passive"))
    )
    (net (code "24") (name "/LED2") (class "Default")
      (node (ref "LED2") (pin "1") (pinfunction "A_1") (pintype "passive"))
      (node (ref "P1") (pin "14") (pinfunction "14_14") (pintype "passive"))
    )
    (net (code "25") (name "/LED3") (class "Default")
      (node (ref "P2") (pin "11") (pinfunction "11_11") (pintype "passive"))
    )
    (net (code "26") (name "/LO1") (class "Default")
      (node (ref "D11") (pin "2") (pinfunction "K_2") (pintype "passive"))
      (node (ref "P1") (pin "26") (pinfunction "26_26") (pintype "passive"))
      (node (ref "R31") (pin "1") (pinfunction "1_1") (pintype "passive"))
    )
    (net (code "27") (name "/LO2") (class "Default")
      (node (ref "D9") (pin "2") (pinfunction "K_2") (pintype "passive"))
      (node (ref "P1") (pin "10") (pinfunction "10_10") (pintype "passive"))
      (node (ref "R29") (pin "1") (pinfunction "1_1") (pintype "passive"))
    )
    (net (code "28") (name "/LO3") (class "Default")
      (node (ref "D7") (pin "2") (pinfunction "K_2") (pintype "passive"))
      (node (ref "P1") (pin "24") (pinfunction "24_24") (pintype "passive"))
      (node (ref "R27") (pin "1") (pinfunction "1_1") (pintype "passive"))
    )
    (net (code "29") (name "/NRST") (class "Default")
      (node (ref "P2") (pin "23") (pinfunction "23_23") (pintype "passive"))
    )
    (net (code "30") (name "/OC") (class "Default")
      (node (ref "P2") (pin "4") (pinfunction "4_4") (pintype "passive"))
    )
    (net (code "31") (name "/P0.0") (class "Default")
      (node (ref "P2") (pin "22") (pinfunction "22_22") (pintype "passive"))
    )
    (net (code "32") (name "/P0.3") (class "Default")
      (node (ref "R11") (pin "2") (pinfunction "2_2") (pintype "passive"))
    )
    (net (code "33") (name "/P0.4") (class "Default")
      (node (ref "P2") (pin "25") (pinfunction "25_25") (pintype "passive"))
    )
    (net (code "34") (name "/P1.10") (class "Default")
      (node (ref "P1") (pin "5") (pinfunction "5_5") (pintype "passive"))
    )
    (net (code "35") (name "/P1.11") (class "Default")
      (node (ref "P1") (pin "18") (pinfunction "18_18") (pintype "passive"))
    )
    (net (code "36") (name "/P2.2") (class "Default")
      (node (ref "P2") (pin "18") (pinfunction "18_18") (pintype "passive"))
    )
    (net (code "37") (name "/P2.3") (class "Default")
      (node (ref "P2") (pin "5") (pinfunction "5_5") (pintype "passive"))
    )
    (net (code "38") (name "/P2.10") (class "Default")
      (node (ref "P2") (pin "17") (pinfunction "17_17") (pintype "passive"))
    )
    (net (code "39") (name "/PA") (class "Default")
      (node (ref "P1") (pin "4") (pinfunction "4_4") (pintype "passive"))
      (node (ref "R55") (pin "1") (pinfunction "1_1") (pintype "passive"))
    )
    (net (code "40") (name "/PB") (class "Default")
      (node (ref "P1") (pin "3") (pinfunction "3_3") (pintype "passive"))
      (node (ref "R59") (pin "1") (pinfunction "1_1") (pintype "passive"))
    )
    (net (code "41") (name "/PC") (class "Default")
      (node (ref "P1") (pin "17") (pinfunction "17_17") (pintype "passive"))
      (node (ref "R61") (pin "1") (pinfunction "1_1") (pintype "passive"))
    )
    (net (code "42") (name "/RXD0") (class "Default")
      (node (ref "P1") (pin "13") (pinfunction "13_13") (pintype "passive"))
      (node (ref "R9") (pin "1") (pinfunction "1_1") (pintype "passive"))
    )
    (net (code "43") (name "/RXD1") (class "Default")
      (node (ref "P2") (pin "12") (pinfunction "12_12") (pintype "passive"))
    )
    (net (code "44") (name "/SPin") (class "Default")
      (node (ref "C19") (pin "2") (pinfunction "2_2") (pintype "passive"))
      (node (ref "P2") (pin "26") (pinfunction "26_26") (pintype "passive"))
      (node (ref "R42") (pin "2") (pinfunction "2_2") (pintype "passive"))
      (node (ref "R43") (pin "2") (pinfunction "2_2") (pintype "passive"))
    )
    (net (code "45") (name "/START1") (class "Default")
      (node (ref "C2") (pin "2") (pinfunction "2_2") (pintype "passive"))
      (node (ref "P1") (pin "28") (pinfunction "28_28") (pintype "passive"))
      (node (ref "R7") (pin "2") (pinfunction "2_2") (pintype "passive"))
      (node (ref "START") (pin "2") (pinfunction "2_2") (pintype "passive"))
      (node (ref "START") (pin "4") (pinfunction "4_4") (pintype "passive"))
    )
    (net (code "46") (name "/STOP1") (class "Default")
      (node (ref "C3") (pin "1") (pinfunction "1_1") (pintype "passive"))
      (node (ref "P1") (pin "12") (pinfunction "12_12") (pintype "passive"))
      (node (ref "R13") (pin "1") (pinfunction "1_1") (pintype "passive"))
      (node (ref "STOP") (pin "2") (pinfunction "2_2") (pintype "passive"))
      (node (ref "STOP") (pin "4") (pinfunction "4_4") (pintype "passive"))
    )
    (net (code "47") (name "/TXD0") (class "Default")
      (node (ref "P1") (pin "27") (pinfunction "27_27") (pintype "passive"))
      (node (ref "R12") (pin "2") (pinfunction "2_2") (pintype "passive"))
    )
    (net (code "48") (name "/TXD1") (class "Default")
      (node (ref "P2") (pin "13") (pinfunction "13_13") (pintype "passive"))
    )
    (net (code "49") (name "/VB1") (class "Default")
      (node (ref "C27") (pin "1") (pinfunction "1_1") (pintype "passive"))
      (node (ref "P1") (pin "8") (pinfunction "8_8") (pintype "passive"))
      (node (ref "R77") (pin "1") (pinfunction "1_1") (pintype "passive"))
    )
    (net (code "50") (name "/VB2") (class "Default")
      (node (ref "C26") (pin "1") (pinfunction "1_1") (pintype "passive"))
      (node (ref "P1") (pin "21") (pinfunction "21_21") (pintype "passive"))
      (node (ref "R78") (pin "1") (pinfunction "1_1") (pintype "passive"))
    )
    (net (code "51") (name "/VB3") (class "Default")
      (node (ref "C25") (pin "1") (pinfunction "1_1") (pintype "passive"))
      (node (ref "P1") (pin "19") (pinfunction "19_19") (pintype "passive"))
      (node (ref "R79") (pin "1") (pinfunction "1_1") (pintype "passive"))
    )
    (net (code "52") (name "/Vol_ADC") (class "Default")
      (node (ref "P2") (pin "3") (pinfunction "3_3") (pintype "passive"))
      (node (ref "R75") (pin "2") (pinfunction "2_2") (pintype "passive"))
    )
    (net (code "53") (name "/ZB") (class "Default")
      (node (ref "R4") (pin "3") (pinfunction "BOT_3") (pintype "passive"))
      (node (ref "R4") (pin "5") (pinfunction "TAP_5") (pintype "passive"))
      (node (ref "R42") (pin "1") (pinfunction "1_1") (pintype "passive"))
    )
    (net (code "56") (name "5V-T") (class "Default")
      (node (ref "C45") (pin "2") (pinfunction "2_2") (pintype "passive"))
      (node (ref "D5") (pin "2") (pinfunction "K_2") (pintype "passive"))
      (node (ref "R73") (pin "2") (pinfunction "2_2") (pintype "passive"))
    )
    (net (code "57") (name "5VH") (class "Default")
      (node (ref "C10") (pin "1") (pinfunction "1_1") (pintype "passive"))
      (node (ref "C43") (pin "2") (pinfunction "2_2") (pintype "passive"))
      (node (ref "D6") (pin "2") (pinfunction "K_2") (pintype "passive"))
      (node (ref "P21") (pin "5") (pinfunction "5_5") (pintype "passive"))
      (node (ref "R51") (pin "2") (pinfunction "2_2") (pintype "passive"))
      (node (ref "R52") (pin "2") (pinfunction "2_2") (pintype "passive"))
      (node (ref "R53") (pin "2") (pinfunction "2_2") (pintype "passive"))
    )
    (net (code "58") (name "GND") (class "Default")
      (node (ref "C10") (pin "2") (pinfunction "2_2") (pintype "passive"))
      (node (ref "C12") (pin "2") (pinfunction "2_2") (pintype "passive"))
      (node (ref "C15") (pin "1") (pinfunction "1_1") (pintype "passive"))
      (node (ref "C19") (pin "1") (pinfunction "1_1") (pintype "passive"))
      (node (ref "C2") (pin "1") (pinfunction "1_1") (pintype "passive"))
      (node (ref "C23") (pin "1") (pinfunction "1_1") (pintype "passive"))
      (node (ref "C3") (pin "2") (pinfunction "2_2") (pintype "passive"))
      (node (ref "C37") (pin "1") (pinfunction "1_1") (pintype "passive"))
      (node (ref "C43") (pin "1") (pinfunction "1_1") (pintype "passive"))
      (node (ref "C45") (pin "1") (pinfunction "1_1") (pintype "passive"))
      (node (ref "C6") (pin "1") (pinfunction "1_1") (pintype "passive"))
      (node (ref "CE1") (pin "2") (pinfunction "2_2") (pintype "passive"))
      (node (ref "CE3") (pin "2") (pinfunction "2_2") (pintype "passive"))
      (node (ref "CE4") (pin "2") (pinfunction "2_2") (pintype "passive"))
      (node (ref "CE5") (pin "2") (pinfunction "2_2") (pintype "passive"))
      (node (ref "D14") (pin "1") (pinfunction "1_1") (pintype "passive"))
      (node (ref "G2") (pin "1") (pinfunction "1_1") (pintype "passive"))
      (node (ref "G4") (pin "1") (pinfunction "1_1") (pintype "passive"))
      (node (ref "G7") (pin "1") (pinfunction "1_1") (pintype "passive"))
      (node (ref "GND") (pin "1") (pinfunction "1_1") (pintype "passive"))
      (node (ref "LED_POWER") (pin "2") (pinfunction "K_2") (pintype "passive"))
      (node (ref "P2") (pin "16") (pinfunction "16_16") (pintype "passive"))
      (node (ref "P2") (pin "27") (pinfunction "27_27") (pintype "passive"))
      (node (ref "P2") (pin "28") (pinfunction "28_28") (pintype "passive"))
      (node (ref "P21") (pin "1") (pinfunction "1_1") (pintype "passive"))
      (node (ref "P4") (pin "1") (pinfunction "1_1") (pintype "passive"))
      (node (ref "R10") (pin "2") (pinfunction "2_2") (pintype "passive"))
      (node (ref "R14") (pin "2") (pinfunction "2_2") (pintype "passive"))
      (node (ref "R35") (pin "2") (pinfunction "2_2") (pintype "passive"))
      (node (ref "R4") (pin "2") (pinfunction "TAP_2") (pintype "passive"))
      (node (ref "R4") (pin "4") (pinfunction "BOT_4") (pintype "passive"))
      (node (ref "R43") (pin "1") (pinfunction "1_1") (pintype "passive"))
      (node (ref "R69") (pin "2") (pinfunction "2_2") (pintype "passive"))
      (node (ref "START") (pin "1") (pinfunction "1_1") (pintype "passive"))
      (node (ref "START") (pin "3") (pinfunction "3_3") (pintype "passive"))
      (node (ref "STOP") (pin "1") (pinfunction "1_1") (pintype "passive"))
      (node (ref "STOP") (pin "3") (pinfunction "3_3") (pintype "passive"))
      (node (ref "U3") (pin "2") (pinfunction "GND_2") (pintype "passive"))
    )
    (net (code "59") (name "Net-(AH-G)") (class "Default")
      (node (ref "AH") (pin "1") (pinfunction "G_1") (pintype "passive"))
      (node (ref "C7") (pin "1") (pinfunction "1_1") (pintype "passive"))
      (node (ref "K26") (pin "2") (pinfunction "2_2") (pintype "passive"))
      (node (ref "R20") (pin "1") (pinfunction "1_1") (pintype "passive"))
    )
    (net (code "60") (name "Net-(AL-G)") (class "Default")
      (node (ref "AL") (pin "1") (pinfunction "G_1") (pintype "passive"))
      (node (ref "C11") (pin "1") (pinfunction "1_1") (pintype "passive"))
      (node (ref "R21") (pin "1") (pinfunction "1_1") (pintype "passive"))
      (node (ref "R27") (pin "2") (pinfunction "2_2") (pintype "passive"))
    )
    (net (code "61") (name "Net-(BH-G)") (class "Default")
      (node (ref "BH") (pin "1") (pinfunction "G_1") (pintype "passive"))
      (node (ref "C16") (pin "1") (pinfunction "1_1") (pintype "passive"))
      (node (ref "R22") (pin "1") (pinfunction "1_1") (pintype "passive"))
      (node (ref "R28") (pin "2") (pinfunction "2_2") (pintype "passive"))
    )
    (net (code "62") (name "Net-(BL-G)") (class "Default")
      (node (ref "BL") (pin "1") (pinfunction "G_1") (pintype "passive"))
      (node (ref "C20") (pin "1") (pinfunction "1_1") (pintype "passive"))
      (node (ref "R23") (pin "1") (pinfunction "1_1") (pintype "passive"))
      (node (ref "R29") (pin "2") (pinfunction "2_2") (pintype "passive"))
    )
    (net (code "63") (name "Net-(CE3-Pad1)") (class "Default")
      (node (ref "CE3") (pin "1") (pinfunction "1_1") (pintype "passive"))
      (node (ref "D13") (pin "2") (pinfunction "2_2") (pintype "passive"))
      (node (ref "R36") (pin "2") (pinfunction "2_2") (pintype "passive"))
      (node (ref "U4") (pin "5") (pinfunction "DRAIN_5") (pintype "passive"))
      (node (ref "U4") (pin "6") (pinfunction "DRAIN_6") (pintype "passive"))
    )
    (net (code "64") (name "Net-(CH-G)") (class "Default")
      (node (ref "C24") (pin "1") (pinfunction "1_1") (pintype "passive"))
      (node (ref "CH") (pin "1") (pinfunction "G_1") (pintype "passive"))
      (node (ref "R24") (pin "1") (pinfunction "1_1") (pintype "passive"))
      (node (ref "R30") (pin "2") (pinfunction "2_2") (pintype "passive"))
    )
    (net (code "65") (name "Net-(CL-G)") (class "Default")
      (node (ref "C34") (pin "1") (pinfunction "1_1") (pintype "passive"))
      (node (ref "CL") (pin "1") (pinfunction "G_1") (pintype "passive"))
      (node (ref "R25") (pin "1") (pinfunction "1_1") (pintype "passive"))
      (node (ref "R31") (pin "2") (pinfunction "2_2") (pintype "passive"))
    )
    (net (code "66") (name "Net-(D1-K)") (class "Default")
      (node (ref "D1") (pin "2") (pinfunction "K_2") (pintype "passive"))
      (node (ref "R79") (pin "2") (pinfunction "2_2") (pintype "passive"))
    )
    (net (code "67") (name "Net-(D2-K)") (class "Default")
      (node (ref "D2") (pin "2") (pinfunction "K_2") (pintype "passive"))
      (node (ref "R78") (pin "2") (pinfunction "2_2") (pintype "passive"))
    )
    (net (code "68") (name "Net-(D3-A)") (class "Default")
      (node (ref "D3") (pin "1") (pinfunction "A_1") (pintype "passive"))
      (node (ref "R20") (pin "2") (pinfunction "2_2") (pintype "passive"))
    )
    (net (code "69") (name "Net-(D4-K)") (class "Default")
      (node (ref "D4") (pin "2") (pinfunction "K_2") (pintype "passive"))
      (node (ref "R77") (pin "2") (pinfunction "2_2") (pintype "passive"))
    )
    (net (code "70") (name "Net-(D7-A)") (class "Default")
      (node (ref "D7") (pin "1") (pinfunction "A_1") (pintype "passive"))
      (node (ref "R21") (pin "2") (pinfunction "2_2") (pintype "passive"))
    )
    (net (code "71") (name "Net-(D8-A)") (class "Default")
      (node (ref "D8") (pin "1") (pinfunction "A_1") (pintype "passive"))
      (node (ref "R22") (pin "2") (pinfunction "2_2") (pintype "passive"))
    )
    (net (code "72") (name "Net-(D9-A)") (class "Default")
      (node (ref "D9") (pin "1") (pinfunction "A_1") (pintype "passive"))
      (node (ref "R23") (pin "2") (pinfunction "2_2") (pintype "passive"))
    )
    (net (code "73") (name "Net-(D10-A)") (class "Default")
      (node (ref "D10") (pin "1") (pinfunction "A_1") (pintype "passive"))
      (node (ref "R24") (pin "2") (pinfunction "2_2") (pintype "passive"))
    )
    (net (code "74") (name "Net-(D11-A)") (class "Default")
      (node (ref "D11") (pin "1") (pinfunction "A_1") (pintype "passive"))
      (node (ref "R25") (pin "2") (pinfunction "2_2") (pintype "passive"))
    )
    (net (code "75") (name "Net-(LED1-K)") (class "Default")
      (node (ref "LED1") (pin "2") (pinfunction "K_2") (pintype "passive"))
      (node (ref "R10") (pin "1") (pinfunction "1_1") (pintype "passive"))
    )
    (net (code "76") (name "Net-(LED2-K)") (class "Default")
      (node (ref "LED2") (pin "2") (pinfunction "K_2") (pintype "passive"))
      (node (ref "R14") (pin "1") (pinfunction "1_1") (pintype "passive"))
    )
    (net (code "77") (name "Net-(LED3-A)") (class "Default")
      (node (ref "LED3") (pin "1") (pinfunction "A_1") (pintype "passive"))
      (node (ref "R11") (pin "1") (pinfunction "1_1") (pintype "passive"))
    )
    (net (code "78") (name "Net-(LED_POWER-A)") (class "Default")
      (node (ref "LED_POWER") (pin "1") (pinfunction "A_1") (pintype "passive"))
      (node (ref "R65") (pin "2") (pinfunction "2_2") (pintype "passive"))
    )
    (net (code "79") (name "Net-(P4-Pad2)") (class "Default")
      (node (ref "P4") (pin "2") (pinfunction "2_2") (pintype "passive"))
      (node (ref "R12") (pin "1") (pinfunction "1_1") (pintype "passive"))
    )
    (net (code "80") (name "Net-(P4-Pad3)") (class "Default")
      (node (ref "P4") (pin "3") (pinfunction "3_3") (pintype "passive"))
      (node (ref "R9") (pin "2") (pinfunction "2_2") (pintype "passive"))
    )
    (net (code "81") (name "Net-(R1-Pad1)") (class "Default")
      (node (ref "R1") (pin "1") (pinfunction "1_1") (pintype "passive"))
      (node (ref "R55") (pin "2") (pinfunction "2_2") (pintype "passive"))
    )
    (net (code "82") (name "Net-(R2-Pad1)") (class "Default")
      (node (ref "R2") (pin "1") (pinfunction "1_1") (pintype "passive"))
      (node (ref "R59") (pin "2") (pinfunction "2_2") (pintype "passive"))
    )
    (net (code "83") (name "Net-(R3-Pad1)") (class "Default")
      (node (ref "R3") (pin "1") (pinfunction "1_1") (pintype "passive"))
      (node (ref "R61") (pin "2") (pinfunction "2_2") (pintype "passive"))
    )
    (net (code "84") (name "Net-(R74-Pad2)") (class "Default")
      (node (ref "R74") (pin "2") (pinfunction "2_2") (pintype "passive"))
      (node (ref "R75") (pin "1") (pinfunction "1_1") (pintype "passive"))
    )
    (net (code "85") (name "Net-(U4-CS)") (class "Default")
      (node (ref "R37") (pin "1") (pinfunction "1_1") (pintype "passive"))
      (node (ref "U4") (pin "4") (pinfunction "CS_4") (pintype "passive"))
    )
    (net (code "86") (name "Net-(U4-DT)") (class "Default")
      (node (ref "C4") (pin "2") (pinfunction "2_2") (pintype "passive"))
      (node (ref "D14") (pin "2") (pinfunction "2_2") (pintype "passive"))
      (node (ref "PL1") (pin "2") (pinfunction "2_2") (pintype "passive"))
      (node (ref "R37") (pin "2") (pinfunction "2_2") (pintype "passive"))
      (node (ref "U4") (pin "2") (pinfunction "VC_2") (pintype "passive"))
      (node (ref "U4") (pin "3") (pinfunction "DT_3") (pintype "passive"))
      (node (ref "U4") (pin "7") (pinfunction "NC_7") (pintype "passive"))
      (node (ref "U4") (pin "8") (pinfunction "GND_8") (pintype "passive"))
    )
    (net (code "87") (name "Net-(U4-VIN)") (class "Default")
      (node (ref "C4") (pin "1") (pinfunction "1_1") (pintype "passive"))
      (node (ref "D12") (pin "2") (pinfunction "2_2") (pintype "passive"))
      (node (ref "R36") (pin "1") (pinfunction "1_1") (pintype "passive"))
      (node (ref "U4") (pin "1") (pinfunction "VIN_1") (pintype "passive"))
    )
    (net (code "88") (name "PGND") (class "Default")
      (node (ref "C11") (pin "2") (pinfunction "2_2") (pintype "passive"))
      (node (ref "C20") (pin "2") (pinfunction "2_2") (pintype "passive"))
      (node (ref "C28") (pin "1") (pinfunction "1_1") (pintype "passive"))
      (node (ref "C29") (pin "1") (pinfunction "1_1") (pintype "passive"))
      (node (ref "C30") (pin "1") (pinfunction "1_1") (pintype "passive"))
      (node (ref "C34") (pin "2") (pinfunction "2_2") (pintype "passive"))
      (node (ref "CE2") (pin "2") (pinfunction "2_2") (pintype "passive"))
      (node (ref "G1") (pin "1") (pinfunction "1_1") (pintype "passive"))
      (node (ref "P1") (pin "1") (pinfunction "1_1") (pintype "passive"))
      (node (ref "P1") (pin "2") (pinfunction "2_2") (pintype "passive"))
      (node (ref "P2") (pin "1") (pinfunction "1_1") (pintype "passive"))
      (node (ref "P2") (pin "2") (pinfunction "2_2") (pintype "passive"))
      (node (ref "R15") (pin "2") (pinfunction "2_2") (pintype "passive"))
      (node (ref "R16") (pin "1") (pinfunction "1_1") (pintype "passive"))
      (node (ref "R17") (pin "2") (pinfunction "2_2") (pintype "passive"))
      (node (ref "R32") (pin "1") (pinfunction "1_1") (pintype "passive"))
      (node (ref "R33") (pin "1") (pinfunction "1_1") (pintype "passive"))
      (node (ref "R34") (pin "1") (pinfunction "1_1") (pintype "passive"))
      (node (ref "R49") (pin "2") (pinfunction "2_2") (pintype "passive"))
      (node (ref "R69") (pin "1") (pinfunction "1_1") (pintype "passive"))
    )
  )
)
